# side_panel.net
KiCad netlist of a schematic drawn in EAGLE
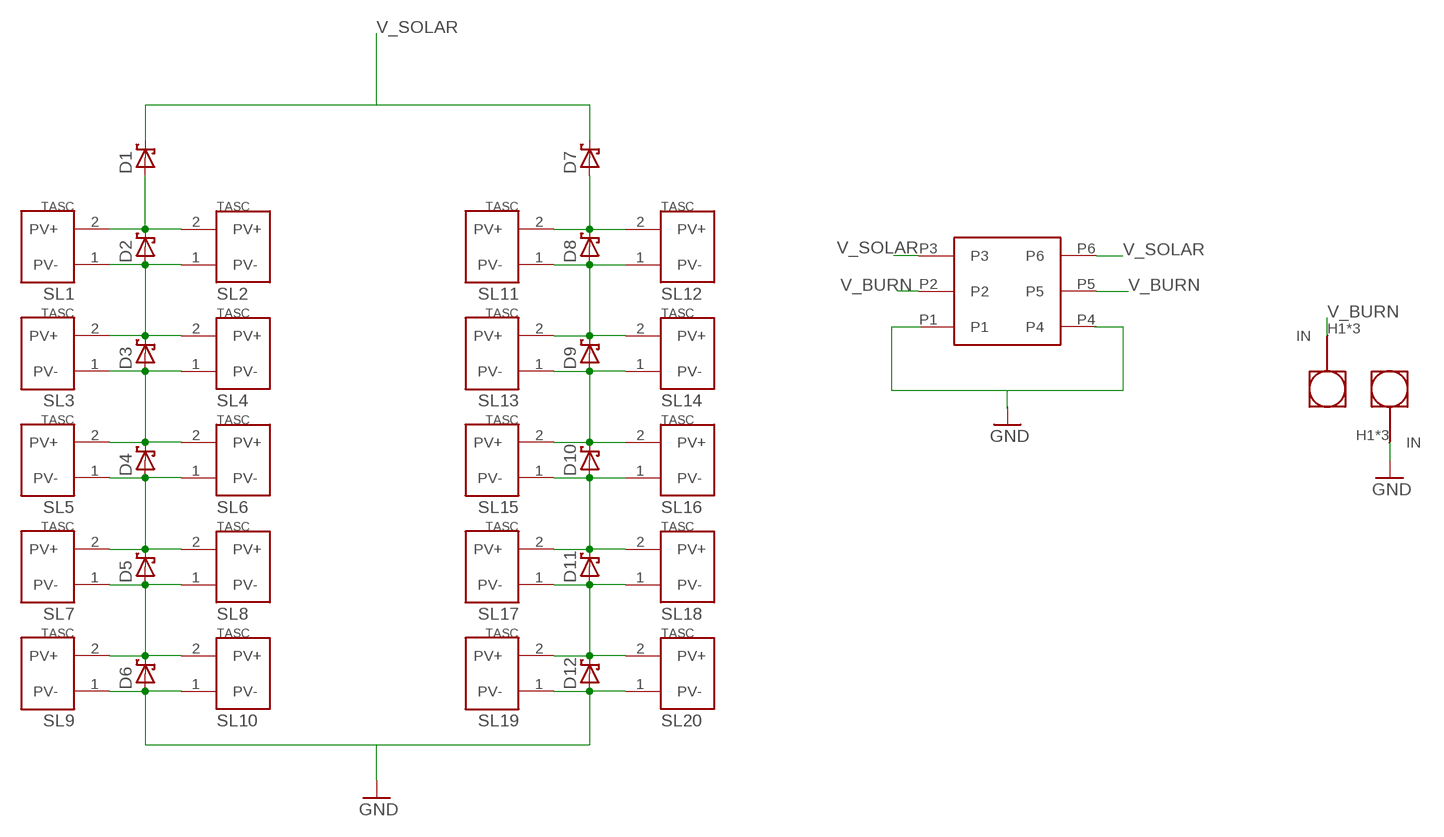
[diagram p0: schematic, sheet 1]

(export (version "E")
  (design (tool "Eeschema 10.0.6"))
  (components
    (comp (ref "D1")
      (value "SB_DIODE")
      (footprint "eagle-import:SB_DIODE")
      (libsource (lib "eagle-import") (part "SB_DIODE"))
    )
    (comp (ref "D2")
      (value "SB_DIODE")
      (footprint "eagle-import:SB_DIODE")
      (libsource (lib "eagle-import") (part "SB_DIODE"))
    )
    (comp (ref "D3")
      (value "SB_DIODE")
      (footprint "eagle-import:SB_DIODE")
      (libsource (lib "eagle-import") (part "SB_DIODE"))
    )
    (comp (ref "D4")
      (value "SB_DIODE")
      (footprint "eagle-import:SB_DIODE")
      (libsource (lib "eagle-import") (part "SB_DIODE"))
    )
    (comp (ref "D5")
      (value "SB_DIODE")
      (footprint "eagle-import:SB_DIODE")
      (libsource (lib "eagle-import") (part "SB_DIODE"))
    )
    (comp (ref "D6")
      (value "SB_DIODE")
      (footprint "eagle-import:SB_DIODE")
      (libsource (lib "eagle-import") (part "SB_DIODE"))
    )
    (comp (ref "D7")
      (value "SB_DIODE")
      (footprint "eagle-import:SB_DIODE")
      (libsource (lib "eagle-import") (part "SB_DIODE"))
    )
    (comp (ref "D8")
      (value "SB_DIODE")
      (footprint "eagle-import:SB_DIODE")
      (libsource (lib "eagle-import") (part "SB_DIODE"))
    )
    (comp (ref "D9")
      (value "SB_DIODE")
      (footprint "eagle-import:SB_DIODE")
      (libsource (lib "eagle-import") (part "SB_DIODE"))
    )
    (comp (ref "D10")
      (value "SB_DIODE")
      (footprint "eagle-import:SB_DIODE")
      (libsource (lib "eagle-import") (part "SB_DIODE"))
    )
    (comp (ref "D11")
      (value "SB_DIODE")
      (footprint "eagle-import:SB_DIODE")
      (libsource (lib "eagle-import") (part "SB_DIODE"))
    )
    (comp (ref "D12")
      (value "SB_DIODE")
      (footprint "eagle-import:SB_DIODE")
      (libsource (lib "eagle-import") (part "SB_DIODE"))
    )
    (comp (ref "SL1")
      (value "SOLAR_CELL")
      (footprint "eagle-import:SOLAR_CELL")
      (libsource (lib "eagle-import") (part "SOLAR_CELL"))
    )
    (comp (ref "SL2")
      (value "SOLAR_CELL")
      (footprint "eagle-import:SOLAR_CELL")
      (libsource (lib "eagle-import") (part "SOLAR_CELL"))
    )
    (comp (ref "SL3")
      (value "SOLAR_CELL")
      (footprint "eagle-import:SOLAR_CELL")
      (libsource (lib "eagle-import") (part "SOLAR_CELL"))
    )
    (comp (ref "SL4")
      (value "SOLAR_CELL")
      (footprint "eagle-import:SOLAR_CELL")
      (libsource (lib "eagle-import") (part "SOLAR_CELL"))
    )
    (comp (ref "SL5")
      (value "SOLAR_CELL")
      (footprint "eagle-import:SOLAR_CELL")
      (libsource (lib "eagle-import") (part "SOLAR_CELL"))
    )
    (comp (ref "SL6")
      (value "SOLAR_CELL")
      (footprint "eagle-import:SOLAR_CELL")
      (libsource (lib "eagle-import") (part "SOLAR_CELL"))
    )
    (comp (ref "SL7")
      (value "SOLAR_CELL")
      (footprint "eagle-import:SOLAR_CELL")
      (libsource (lib "eagle-import") (part "SOLAR_CELL"))
    )
    (comp (ref "SL8")
      (value "SOLAR_CELL")
      (footprint "eagle-import:SOLAR_CELL")
      (libsource (lib "eagle-import") (part "SOLAR_CELL"))
    )
    (comp (ref "SL9")
      (value "SOLAR_CELL")
      (footprint "eagle-import:SOLAR_CELL")
      (libsource (lib "eagle-import") (part "SOLAR_CELL"))
    )
    (comp (ref "SL10")
      (value "SOLAR_CELL")
      (footprint "eagle-import:SOLAR_CELL")
      (libsource (lib "eagle-import") (part "SOLAR_CELL"))
    )
    (comp (ref "SL11")
      (value "SOLAR_CELL")
      (footprint "eagle-import:SOLAR_CELL")
      (libsource (lib "eagle-import") (part "SOLAR_CELL"))
    )
    (comp (ref "SL12")
      (value "SOLAR_CELL")
      (footprint "eagle-import:SOLAR_CELL")
      (libsource (lib "eagle-import") (part "SOLAR_CELL"))
    )
    (comp (ref "SL13")
      (value "SOLAR_CELL")
      (footprint "eagle-import:SOLAR_CELL")
      (libsource (lib "eagle-import") (part "SOLAR_CELL"))
    )
    (comp (ref "SL14")
      (value "SOLAR_CELL")
      (footprint "eagle-import:SOLAR_CELL")
      (libsource (lib "eagle-import") (part "SOLAR_CELL"))
    )
    (comp (ref "SL15")
      (value "SOLAR_CELL")
      (footprint "eagle-import:SOLAR_CELL")
      (libsource (lib "eagle-import") (part "SOLAR_CELL"))
    )
    (comp (ref "SL16")
      (value "SOLAR_CELL")
      (footprint "eagle-import:SOLAR_CELL")
      (libsource (lib "eagle-import") (part "SOLAR_CELL"))
    )
    (comp (ref "SL17")
      (value "SOLAR_CELL")
      (footprint "eagle-import:SOLAR_CELL")
      (libsource (lib "eagle-import") (part "SOLAR_CELL"))
    )
    (comp (ref "SL18")
      (value "SOLAR_CELL")
      (footprint "eagle-import:SOLAR_CELL")
      (libsource (lib "eagle-import") (part "SOLAR_CELL"))
    )
    (comp (ref "SL19")
      (value "SOLAR_CELL")
      (footprint "eagle-import:SOLAR_CELL")
      (libsource (lib "eagle-import") (part "SOLAR_CELL"))
    )
    (comp (ref "SL20")
      (value "SOLAR_CELL")
      (footprint "eagle-import:SOLAR_CELL")
      (libsource (lib "eagle-import") (part "SOLAR_CELL"))
    )
    (comp (ref "U$1")
      (value "G125-FV20605L0P")
      (footprint "eagle-import:G125-FV20605L0P")
      (libsource (lib "eagle-import") (part "G125-FV20605L0P"))
    )
    (comp (ref "U$2")
      (value "BURNER")
      (footprint "eagle-import:BURNER")
      (libsource (lib "eagle-import") (part "BURNER"))
    )
    (comp (ref "U$4")
      (value "BURNER")
      (footprint "eagle-import:BURNER")
      (libsource (lib "eagle-import") (part "BURNER"))
    )
  )
  (nets
    (net (code "1") (name "/V_BURN") (class "Default")
      (node (ref "U$1") (pin "P2") (pinfunction "P2_P2") (pintype "bidirectional"))
      (node (ref "U$1") (pin "P5") (pinfunction "P5_P5") (pintype "bidirectional"))
      (node (ref "U$4") (pin "H1") (pinfunction "IN_H1") (pintype "bidirectional"))
      (node (ref "U$4") (pin "H2") (pinfunction "IN_H2") (pintype "bidirectional"))
      (node (ref "U$4") (pin "H3") (pinfunction "IN_H3") (pintype "bidirectional"))
    )
    (net (code "2") (name "/V_SOLAR") (class "Default")
      (node (ref "D1") (pin "NEG") (pinfunction "NEG_NEG") (pintype "passive"))
      (node (ref "D7") (pin "NEG") (pinfunction "NEG_NEG") (pintype "passive"))
      (node (ref "U$1") (pin "P3") (pinfunction "P3_P3") (pintype "bidirectional"))
      (node (ref "U$1") (pin "P6") (pinfunction "P6_P6") (pintype "bidirectional"))
    )
    (net (code "3") (name "GND") (class "Default")
      (node (ref "D12") (pin "POS") (pinfunction "POS_POS") (pintype "passive"))
      (node (ref "D6") (pin "POS") (pinfunction "POS_POS") (pintype "passive"))
      (node (ref "SL10") (pin "1") (pinfunction "PV-_1") (pintype "bidirectional"))
      (node (ref "SL19") (pin "1") (pinfunction "PV-_1") (pintype "bidirectional"))
      (node (ref "SL20") (pin "1") (pinfunction "PV-_1") (pintype "bidirectional"))
      (node (ref "SL9") (pin "1") (pinfunction "PV-_1") (pintype "bidirectional"))
      (node (ref "U$2") (pin "H1") (pinfunction "IN_H1") (pintype "bidirectional"))
      (node (ref "U$2") (pin "H2") (pinfunction "IN_H2") (pintype "bidirectional"))
      (node (ref "U$2") (pin "H3") (pinfunction "IN_H3") (pintype "bidirectional"))
    )
    (net (code "4") (name "Net-(SL1-PV+)") (class "Default")
      (node (ref "D1") (pin "POS") (pinfunction "POS_POS") (pintype "passive"))
      (node (ref "D2") (pin "NEG") (pinfunction "NEG_NEG") (pintype "passive"))
      (node (ref "SL1") (pin "2") (pinfunction "PV+_2") (pintype "bidirectional"))
      (node (ref "SL2") (pin "2") (pinfunction "PV+_2") (pintype "bidirectional"))
    )
    (net (code "5") (name "Net-(SL1-PV-)") (class "Default")
      (node (ref "D2") (pin "POS") (pinfunction "POS_POS") (pintype "passive"))
      (node (ref "D3") (pin "NEG") (pinfunction "NEG_NEG") (pintype "passive"))
      (node (ref "SL1") (pin "1") (pinfunction "PV-_1") (pintype "bidirectional"))
      (node (ref "SL2") (pin "1") (pinfunction "PV-_1") (pintype "bidirectional"))
      (node (ref "SL3") (pin "2") (pinfunction "PV+_2") (pintype "bidirectional"))
      (node (ref "SL4") (pin "2") (pinfunction "PV+_2") (pintype "bidirectional"))
    )
    (net (code "6") (name "Net-(SL3-PV-)") (class "Default")
      (node (ref "D3") (pin "POS") (pinfunction "POS_POS") (pintype "passive"))
      (node (ref "D4") (pin "NEG") (pinfunction "NEG_NEG") (pintype "passive"))
      (node (ref "SL3") (pin "1") (pinfunction "PV-_1") (pintype "bidirectional"))
      (node (ref "SL4") (pin "1") (pinfunction "PV-_1") (pintype "bidirectional"))
      (node (ref "SL5") (pin "2") (pinfunction "PV+_2") (pintype "bidirectional"))
      (node (ref "SL6") (pin "2") (pinfunction "PV+_2") (pintype "bidirectional"))
    )
    (net (code "7") (name "Net-(SL5-PV-)") (class "Default")
      (node (ref "D4") (pin "POS") (pinfunction "POS_POS") (pintype "passive"))
      (node (ref "D5") (pin "NEG") (pinfunction "NEG_NEG") (pintype "passive"))
      (node (ref "SL5") (pin "1") (pinfunction "PV-_1") (pintype "bidirectional"))
      (node (ref "SL6") (pin "1") (pinfunction "PV-_1") (pintype "bidirectional"))
      (node (ref "SL7") (pin "2") (pinfunction "PV+_2") (pintype "bidirectional"))
      (node (ref "SL8") (pin "2") (pinfunction "PV+_2") (pintype "bidirectional"))
    )
    (net (code "8") (name "Net-(SL10-PV+)") (class "Default")
      (node (ref "D5") (pin "POS") (pinfunction "POS_POS") (pintype "passive"))
      (node (ref "D6") (pin "NEG") (pinfunction "NEG_NEG") (pintype "passive"))
      (node (ref "SL10") (pin "2") (pinfunction "PV+_2") (pintype "bidirectional"))
      (node (ref "SL7") (pin "1") (pinfunction "PV-_1") (pintype "bidirectional"))
      (node (ref "SL8") (pin "1") (pinfunction "PV-_1") (pintype "bidirectional"))
      (node (ref "SL9") (pin "2") (pinfunction "PV+_2") (pintype "bidirectional"))
    )
    (net (code "9") (name "Net-(SL11-PV+)") (class "Default")
      (node (ref "D7") (pin "POS") (pinfunction "POS_POS") (pintype "passive"))
      (node (ref "D8") (pin "NEG") (pinfunction "NEG_NEG") (pintype "passive"))
      (node (ref "SL11") (pin "2") (pinfunction "PV+_2") (pintype "bidirectional"))
      (node (ref "SL12") (pin "2") (pinfunction "PV+_2") (pintype "bidirectional"))
    )
    (net (code "10") (name "Net-(SL11-PV-)") (class "Default")
      (node (ref "D8") (pin "POS") (pinfunction "POS_POS") (pintype "passive"))
      (node (ref "D9") (pin "NEG") (pinfunction "NEG_NEG") (pintype "passive"))
      (node (ref "SL11") (pin "1") (pinfunction "PV-_1") (pintype "bidirectional"))
      (node (ref "SL12") (pin "1") (pinfunction "PV-_1") (pintype "bidirectional"))
      (node (ref "SL13") (pin "2") (pinfunction "PV+_2") (pintype "bidirectional"))
      (node (ref "SL14") (pin "2") (pinfunction "PV+_2") (pintype "bidirectional"))
    )
    (net (code "11") (name "Net-(SL13-PV-)") (class "Default")
      (node (ref "D10") (pin "NEG") (pinfunction "NEG_NEG") (pintype "passive"))
      (node (ref "D9") (pin "POS") (pinfunction "POS_POS") (pintype "passive"))
      (node (ref "SL13") (pin "1") (pinfunction "PV-_1") (pintype "bidirectional"))
      (node (ref "SL14") (pin "1") (pinfunction "PV-_1") (pintype "bidirectional"))
      (node (ref "SL15") (pin "2") (pinfunction "PV+_2") (pintype "bidirectional"))
      (node (ref "SL16") (pin "2") (pinfunction "PV+_2") (pintype "bidirectional"))
    )
    (net (code "12") (name "Net-(SL15-PV-)") (class "Default")
      (node (ref "D10") (pin "POS") (pinfunction "POS_POS") (pintype "passive"))
      (node (ref "D11") (pin "NEG") (pinfunction "NEG_NEG") (pintype "passive"))
      (node (ref "SL15") (pin "1") (pinfunction "PV-_1") (pintype "bidirectional"))
      (node (ref "SL16") (pin "1") (pinfunction "PV-_1") (pintype "bidirectional"))
      (node (ref "SL17") (pin "2") (pinfunction "PV+_2") (pintype "bidirectional"))
      (node (ref "SL18") (pin "2") (pinfunction "PV+_2") (pintype "bidirectional"))
    )
    (net (code "13") (name "Net-(SL17-PV-)") (class "Default")
      (node (ref "D11") (pin "POS") (pinfunction "POS_POS") (pintype "passive"))
      (node (ref "D12") (pin "NEG") (pinfunction "NEG_NEG") (pintype "passive"))
      (node (ref "SL17") (pin "1") (pinfunction "PV-_1") (pintype "bidirectional"))
      (node (ref "SL18") (pin "1") (pinfunction "PV-_1") (pintype "bidirectional"))
      (node (ref "SL19") (pin "2") (pinfunction "PV+_2") (pintype "bidirectional"))
      (node (ref "SL20") (pin "2") (pinfunction "PV+_2") (pintype "bidirectional"))
    )
    (net (code "14") (name "unconnected-(U$1-PadP1)") (class "Default")
      (node (ref "U$1") (pin "P1") (pinfunction "P1_P1") (pintype "bidirectional"))
    )
    (net (code "15") (name "unconnected-(U$1-PadP4)") (class "Default")
      (node (ref "U$1") (pin "P4") (pinfunction "P4_P4") (pintype "bidirectional"))
    )
  )
)
